# uMultimeter_ExpBreadBoard_Sch.net
KiCad netlist of a schematic drawn in Altium Designer
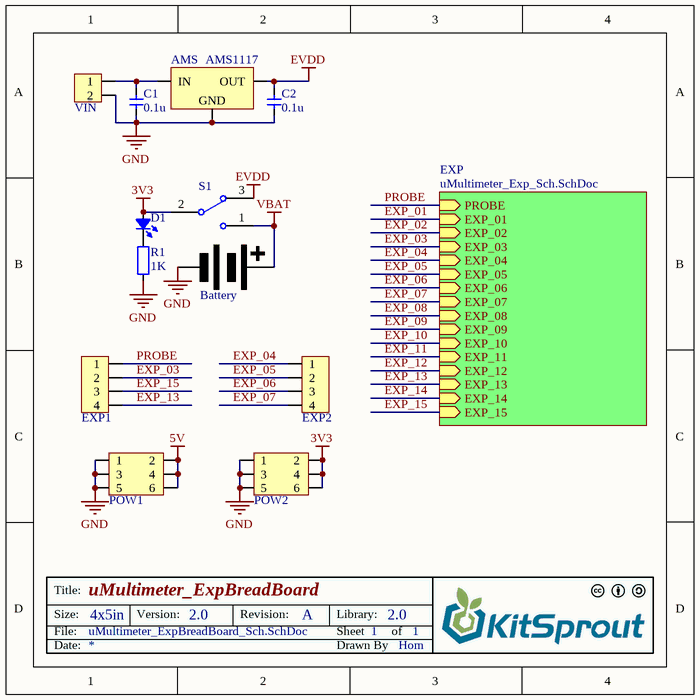
[diagram p0: uMultimeter_ExpBreadBoard_Sch.SchDoc]

(export (version "E")
  (design (tool "Eeschema 10.0.6"))
  (components
    (comp (ref "AMS")
      (value "AMS1117")
      (footprint "PCB_IntegratedCircuit:SOT223-3")
      (description "Power")
      (libsource (lib "SCH_IntegratedCircuit") (part "AMS1117"))
    )
    (comp (ref "Battery")
      (value "Battery")
      (footprint "PCB_Battery:CR2032-1")
      (libsource (lib "SCH_Battery") (part "Battery"))
    )
    (comp (ref "C1")
      (value "0.1u")
      (footprint "PCB_PassiveCap:CAP_0603")
      (description "Capacitor")
      (fields (field (name "Comment") "Cap_0603"))
      (libsource (lib "SCH_Passive") (part "Cap_0603"))
    )
    (comp (ref "C2")
      (value "0.1u")
      (footprint "PCB_PassiveCap:CAP_0603")
      (description "Capacitor")
      (fields (field (name "Comment") "Cap_0603"))
      (libsource (lib "SCH_Passive") (part "Cap_0603"))
    )
    (comp (ref "D1")
      (value "LED_0805")
      (footprint "PCB_ActiveLED:LED_0805_BLUE")
      (description "LED")
      (libsource (lib "SCH_Active") (part "LED_0805"))
    )
    (comp (ref "EXP1")
      (value "HDR1x4_2.54")
      (footprint "PCB_ConnectorHDR:HDR1x4_2.54_180")
      (description "Header")
      (libsource (lib "SCH_ConnectorHDR") (part "HDR1x4_2.54T"))
    )
    (comp (ref "EXP2")
      (value "HDR1x4_2.54")
      (footprint "PCB_ConnectorHDR:HDR1x4_2.54_180")
      (description "Header")
      (libsource (lib "SCH_ConnectorHDR") (part "HDR1x4_2.54"))
    )
    (comp (ref "POW1")
      (value "HDR2x3_2.54")
      (footprint "PCB_ConnectorHDR:HDR2X3_2.54_180")
      (description "Header")
      (libsource (lib "SCH_ConnectorHDR") (part "HDR2x3_2.54"))
    )
    (comp (ref "POW2")
      (value "HDR2x3_2.54")
      (footprint "PCB_ConnectorHDR:HDR2X3_2.54_180")
      (description "Header")
      (libsource (lib "SCH_ConnectorHDR") (part "HDR2x3_2.54"))
    )
    (comp (ref "R1")
      (value "1K")
      (footprint "PCB_PassiveRes:RES_0603")
      (description "Resistor")
      (fields (field (name "Comment") "Res_0603"))
      (libsource (lib "SCH_Passive") (part "Res_0603"))
    )
    (comp (ref "S1")
      (value "SwitchSPDT_2.8x6.6_90")
      (footprint "PCB_Switch:SwitchSPDT_2.8X6.6_90")
      (description "Switch")
      (libsource (lib "SCH_Switch") (part "SwitchSPDT_2.8x6.6_90"))
    )
    (comp (ref "VIN")
      (value "HDR1x2_2.54")
      (footprint "PCB_ConnectorHDR:HDR1X2_2.54_90")
      (description "Header")
      (libsource (lib "SCH_ConnectorHDR") (part "HDR1x2_2.54T"))
    )
  )
  (nets
    (net (code "3") (name "/EXP_03") (class "Default")
      (node (ref "EXP1") (pin "2") (pinfunction "2_2") (pintype "passive"))
    )
    (net (code "4") (name "/EXP_04") (class "Default")
      (node (ref "EXP2") (pin "1") (pinfunction "1_1") (pintype "passive"))
    )
    (net (code "5") (name "/EXP_05") (class "Default")
      (node (ref "EXP2") (pin "2") (pinfunction "2_2") (pintype "passive"))
    )
    (net (code "6") (name "/EXP_06") (class "Default")
      (node (ref "EXP2") (pin "3") (pinfunction "3_3") (pintype "passive"))
    )
    (net (code "7") (name "/EXP_07") (class "Default")
      (node (ref "EXP2") (pin "4") (pinfunction "4_4") (pintype "passive"))
    )
    (net (code "13") (name "/EXP_13") (class "Default")
      (node (ref "EXP1") (pin "4") (pinfunction "4_4") (pintype "passive"))
    )
    (net (code "15") (name "/EXP_15") (class "Default")
      (node (ref "EXP1") (pin "3") (pinfunction "3_3") (pintype "passive"))
    )
    (net (code "16") (name "/PROBE") (class "Default")
      (node (ref "EXP1") (pin "1") (pinfunction "1_1") (pintype "passive"))
    )
    (net (code "17") (name "3V3") (class "Default")
      (node (ref "D1") (pin "1") (pinfunction "A_1") (pintype "passive"))
      (node (ref "POW2") (pin "2") (pinfunction "2_2") (pintype "passive"))
      (node (ref "POW2") (pin "4") (pinfunction "4_4") (pintype "passive"))
      (node (ref "POW2") (pin "6") (pinfunction "6_6") (pintype "passive"))
      (node (ref "S1") (pin "2") (pinfunction "2_2") (pintype "passive"))
    )
    (net (code "18") (name "5V") (class "Default")
      (node (ref "POW1") (pin "2") (pinfunction "2_2") (pintype "passive"))
      (node (ref "POW1") (pin "4") (pinfunction "4_4") (pintype "passive"))
      (node (ref "POW1") (pin "6") (pinfunction "6_6") (pintype "passive"))
    )
    (net (code "19") (name "EVDD") (class "Default")
      (node (ref "AMS") (pin "2") (pinfunction "OUT_2") (pintype "power_in"))
      (node (ref "C2") (pin "2") (pinfunction "2_2") (pintype "passive"))
      (node (ref "S1") (pin "3") (pinfunction "3_3") (pintype "passive"))
    )
    (net (code "20") (name "GND") (class "Default")
      (node (ref "AMS") (pin "1") (pinfunction "GND_1") (pintype "power_in"))
      (node (ref "Battery") (pin "1") (pinfunction "-_1") (pintype "passive"))
      (node (ref "C1") (pin "1") (pinfunction "1_1") (pintype "passive"))
      (node (ref "C2") (pin "1") (pinfunction "1_1") (pintype "passive"))
      (node (ref "POW1") (pin "1") (pinfunction "1_1") (pintype "passive"))
      (node (ref "POW1") (pin "3") (pinfunction "3_3") (pintype "passive"))
      (node (ref "POW1") (pin "5") (pinfunction "5_5") (pintype "passive"))
      (node (ref "POW2") (pin "1") (pinfunction "1_1") (pintype "passive"))
      (node (ref "POW2") (pin "3") (pinfunction "3_3") (pintype "passive"))
      (node (ref "POW2") (pin "5") (pinfunction "5_5") (pintype "passive"))
      (node (ref "R1") (pin "2") (pinfunction "2_2") (pintype "passive"))
      (node (ref "VIN") (pin "2") (pinfunction "2_2") (pintype "passive"))
    )
    (net (code "21") (name "Net-(AMS-IN)") (class "Default")
      (node (ref "AMS") (pin "3") (pinfunction "IN_3") (pintype "power_in"))
      (node (ref "C1") (pin "2") (pinfunction "2_2") (pintype "passive"))
      (node (ref "VIN") (pin "1") (pinfunction "1_1") (pintype "passive"))
    )
    (net (code "22") (name "Net-(D1-K)") (class "Default")
      (node (ref "D1") (pin "2") (pinfunction "K_2") (pintype "passive"))
      (node (ref "R1") (pin "1") (pinfunction "1_1") (pintype "passive"))
    )
    (net (code "23") (name "VBAT") (class "Default")
      (node (ref "Battery") (pin "2") (pinfunction "+_2") (pintype "passive"))
      (node (ref "S1") (pin "1") (pinfunction "1_1") (pintype "passive"))
    )
  )
)
